# input_signal_conditioning.net
KiCad netlist of a schematic drawn in Altium Designer
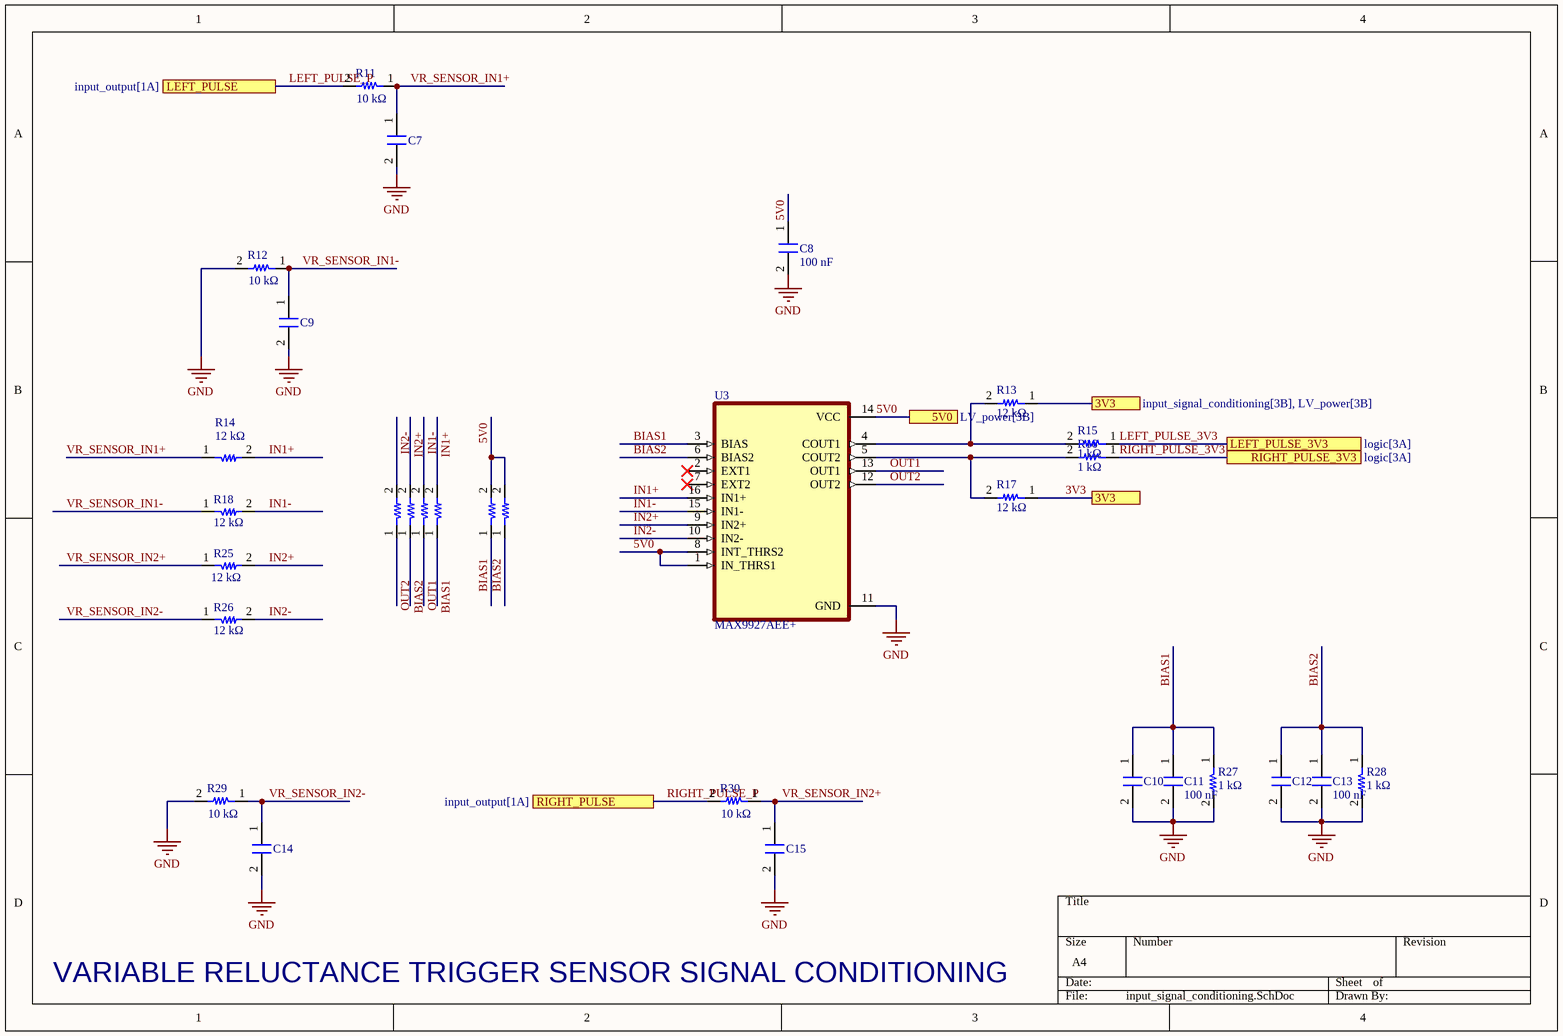
[diagram p0: input_signal_conditioning.SchDoc]

(export (version "E")
  (design (tool "Eeschema 10.0.6"))
  (components
    (comp (ref "C7")
      (value "Capacitor_0402")
      (footprint "0402_fp")
      (libsource (lib "RC_sch") (part "Capacitor_0402"))
    )
    (comp (ref "C8")
      (value "100 nF")
      (footprint "0402_fp")
      (fields (field (name "Comment") "Capacitor_0402"))
      (libsource (lib "RC_sch") (part "Capacitor_0402"))
    )
    (comp (ref "C9")
      (value "Capacitor_0402")
      (footprint "0402_fp")
      (libsource (lib "RC_sch") (part "Capacitor_0402"))
    )
    (comp (ref "C10")
      (value "Capacitor_0603")
      (footprint "0603_FP")
      (libsource (lib "RC_sch") (part "Capacitor_0603"))
    )
    (comp (ref "C11")
      (value "100 nF")
      (footprint "0402_fp")
      (fields (field (name "Comment") "Capacitor_0402"))
      (libsource (lib "RC_sch") (part "Capacitor_0402"))
    )
    (comp (ref "C12")
      (value "Capacitor_0603")
      (footprint "0603_FP")
      (libsource (lib "RC_sch") (part "Capacitor_0603"))
    )
    (comp (ref "C13")
      (value "100 nF")
      (footprint "0402_fp")
      (fields (field (name "Comment") "Capacitor_0402"))
      (libsource (lib "RC_sch") (part "Capacitor_0402"))
    )
    (comp (ref "C14")
      (value "Capacitor_0402")
      (footprint "0402_fp")
      (libsource (lib "RC_sch") (part "Capacitor_0402"))
    )
    (comp (ref "C15")
      (value "Capacitor_0402")
      (footprint "0402_fp")
      (libsource (lib "RC_sch") (part "Capacitor_0402"))
    )
    (comp (ref "R11")
      (value "10 kΩ")
      (footprint "0402_fp")
      (fields (field (name "Comment") "Resistor_0402"))
      (libsource (lib "RC_sch") (part "Resistor_0402"))
    )
    (comp (ref "R12")
      (value "10 kΩ")
      (footprint "0402_fp")
      (fields (field (name "Comment") "Resistor_0402"))
      (libsource (lib "RC_sch") (part "Resistor_0402"))
    )
    (comp (ref "R13")
      (value "12 kΩ")
      (footprint "0402_fp")
      (fields (field (name "Comment") "Resistor_0402"))
      (libsource (lib "RC_sch") (part "Resistor_0402"))
    )
    (comp (ref "R14")
      (value "12 kΩ")
      (footprint "0402_fp")
      (fields (field (name "Comment") "Resistor_0402"))
      (libsource (lib "RC_sch") (part "Resistor_0402"))
    )
    (comp (ref "R15")
      (value "1 kΩ")
      (footprint "0402_fp")
      (fields (field (name "Comment") "Resistor_0402"))
      (libsource (lib "RC_sch") (part "Resistor_0402"))
    )
    (comp (ref "R16")
      (value "1 kΩ")
      (footprint "0402_fp")
      (fields (field (name "Comment") "Resistor_0402"))
      (libsource (lib "RC_sch") (part "Resistor_0402"))
    )
    (comp (ref "R17")
      (value "12 kΩ")
      (footprint "0402_fp")
      (fields (field (name "Comment") "Resistor_0402"))
      (libsource (lib "RC_sch") (part "Resistor_0402"))
    )
    (comp (ref "R18")
      (value "12 kΩ")
      (footprint "0402_fp")
      (fields (field (name "Comment") "Resistor_0402"))
      (libsource (lib "RC_sch") (part "Resistor_0402"))
    )
    (comp (ref "R19")
      (value "Resistor_0402")
      (footprint "0402_fp")
      (libsource (lib "RC_sch") (part "Resistor_0402"))
    )
    (comp (ref "R20")
      (value "Resistor_0402")
      (footprint "0402_fp")
      (libsource (lib "RC_sch") (part "Resistor_0402"))
    )
    (comp (ref "R21")
      (value "Resistor_0402")
      (footprint "0402_fp")
      (libsource (lib "RC_sch") (part "Resistor_0402"))
    )
    (comp (ref "R22")
      (value "Resistor_0402")
      (footprint "0402_fp")
      (libsource (lib "RC_sch") (part "Resistor_0402"))
    )
    (comp (ref "R23")
      (value "Resistor_0402")
      (footprint "0402_fp")
      (libsource (lib "RC_sch") (part "Resistor_0402"))
    )
    (comp (ref "R24")
      (value "Resistor_0402")
      (footprint "0402_fp")
      (libsource (lib "RC_sch") (part "Resistor_0402"))
    )
    (comp (ref "R25")
      (value "12 kΩ")
      (footprint "0402_fp")
      (fields (field (name "Comment") "Resistor_0402"))
      (libsource (lib "RC_sch") (part "Resistor_0402"))
    )
    (comp (ref "R26")
      (value "12 kΩ")
      (footprint "0402_fp")
      (fields (field (name "Comment") "Resistor_0402"))
      (libsource (lib "RC_sch") (part "Resistor_0402"))
    )
    (comp (ref "R27")
      (value "1 kΩ")
      (footprint "0402_fp")
      (fields (field (name "Comment") "Resistor_0402"))
      (libsource (lib "RC_sch") (part "Resistor_0402"))
    )
    (comp (ref "R28")
      (value "1 kΩ")
      (footprint "0402_fp")
      (fields (field (name "Comment") "Resistor_0402"))
      (libsource (lib "RC_sch") (part "Resistor_0402"))
    )
    (comp (ref "R29")
      (value "10 kΩ")
      (footprint "0402_fp")
      (fields (field (name "Comment") "Resistor_0402"))
      (libsource (lib "RC_sch") (part "Resistor_0402"))
    )
    (comp (ref "R30")
      (value "10 kΩ")
      (footprint "0402_fp")
      (fields (field (name "Comment") "Resistor_0402"))
      (libsource (lib "RC_sch") (part "Resistor_0402"))
    )
    (comp (ref "U3")
      (value "MAX9927AEE+")
      (footprint "SOP63P602X175-16N")
      (description "Variable-Reluctance Sensor Interface with Differential Input and Adaptive Peak Threshold")
      (fields (field (name "MF") "Analog Devices"))
      (libsource (lib "MAX9927AEE+") (part "MAX9927AEE+"))
    )
  )
  (nets
    (net (code "1") (name "/3V3") (class "Default")
      (node (ref "R13") (pin "1") (pinfunction "1_1") (pintype "passive"))
      (node (ref "R17") (pin "1") (pinfunction "1_1") (pintype "passive"))
    )
    (net (code "2") (name "/5V0") (class "Default")
      (node (ref "C8") (pin "1") (pinfunction "1_1") (pintype "passive"))
      (node (ref "R23") (pin "2") (pinfunction "2_2") (pintype "passive"))
      (node (ref "R24") (pin "2") (pinfunction "2_2") (pintype "passive"))
      (node (ref "U3") (pin "1") (pinfunction "IN_THRS1_1") (pintype "input"))
      (node (ref "U3") (pin "14") (pinfunction "VCC_14") (pintype "power_in"))
      (node (ref "U3") (pin "8") (pinfunction "INT_THRS2_8") (pintype "input"))
    )
    (net (code "3") (name "/BIAS1") (class "Default")
      (node (ref "C10") (pin "1") (pinfunction "1_1") (pintype "passive"))
      (node (ref "C11") (pin "1") (pinfunction "1_1") (pintype "passive"))
      (node (ref "R22") (pin "1") (pinfunction "1_1") (pintype "passive"))
      (node (ref "R23") (pin "1") (pinfunction "1_1") (pintype "passive"))
      (node (ref "R27") (pin "1") (pinfunction "1_1") (pintype "passive"))
      (node (ref "U3") (pin "3") (pinfunction "BIAS_3") (pintype "input"))
    )
    (net (code "4") (name "/BIAS2") (class "Default")
      (node (ref "C12") (pin "1") (pinfunction "1_1") (pintype "passive"))
      (node (ref "C13") (pin "1") (pinfunction "1_1") (pintype "passive"))
      (node (ref "R20") (pin "1") (pinfunction "1_1") (pintype "passive"))
      (node (ref "R24") (pin "1") (pinfunction "1_1") (pintype "passive"))
      (node (ref "R28") (pin "1") (pinfunction "1_1") (pintype "passive"))
      (node (ref "U3") (pin "6") (pinfunction "BIAS2_6") (pintype "input"))
    )
    (net (code "5") (name "/IN1+") (class "Default")
      (node (ref "R14") (pin "2") (pinfunction "2_2") (pintype "passive"))
      (node (ref "R22") (pin "2") (pinfunction "2_2") (pintype "passive"))
      (node (ref "U3") (pin "16") (pinfunction "IN1+_16") (pintype "input"))
    )
    (net (code "6") (name "/IN1-") (class "Default")
      (node (ref "R18") (pin "2") (pinfunction "2_2") (pintype "passive"))
      (node (ref "R21") (pin "2") (pinfunction "2_2") (pintype "passive"))
      (node (ref "U3") (pin "15") (pinfunction "IN1-_15") (pintype "input"))
    )
    (net (code "7") (name "/IN2+") (class "Default")
      (node (ref "R20") (pin "2") (pinfunction "2_2") (pintype "passive"))
      (node (ref "R25") (pin "2") (pinfunction "2_2") (pintype "passive"))
      (node (ref "U3") (pin "9") (pinfunction "IN2+_9") (pintype "input"))
    )
    (net (code "8") (name "/IN2-") (class "Default")
      (node (ref "R19") (pin "2") (pinfunction "2_2") (pintype "passive"))
      (node (ref "R26") (pin "2") (pinfunction "2_2") (pintype "passive"))
      (node (ref "U3") (pin "10") (pinfunction "IN2-_10") (pintype "input"))
    )
    (net (code "9") (name "/LEFT_PULSE_3V3") (class "Default")
      (node (ref "R15") (pin "1") (pinfunction "1_1") (pintype "passive"))
    )
    (net (code "10") (name "/LEFT_PULSE_P") (class "Default")
      (node (ref "R11") (pin "2") (pinfunction "2_2") (pintype "passive"))
    )
    (net (code "11") (name "/OUT1") (class "Default")
      (node (ref "R21") (pin "1") (pinfunction "1_1") (pintype "passive"))
      (node (ref "U3") (pin "13") (pinfunction "OUT1_13") (pintype "output"))
    )
    (net (code "12") (name "/OUT2") (class "Default")
      (node (ref "R19") (pin "1") (pinfunction "1_1") (pintype "passive"))
      (node (ref "U3") (pin "12") (pinfunction "OUT2_12") (pintype "output"))
    )
    (net (code "13") (name "/RIGHT_PULSE_3V3") (class "Default")
      (node (ref "R16") (pin "1") (pinfunction "1_1") (pintype "passive"))
    )
    (net (code "14") (name "/RIGHT_PULSE_P") (class "Default")
      (node (ref "R30") (pin "2") (pinfunction "2_2") (pintype "passive"))
    )
    (net (code "15") (name "/VR_SENSOR_IN1+") (class "Default")
      (node (ref "C7") (pin "1") (pinfunction "1_1") (pintype "passive"))
      (node (ref "R11") (pin "1") (pinfunction "1_1") (pintype "passive"))
      (node (ref "R14") (pin "1") (pinfunction "1_1") (pintype "passive"))
    )
    (net (code "16") (name "/VR_SENSOR_IN1-") (class "Default")
      (node (ref "C9") (pin "1") (pinfunction "1_1") (pintype "passive"))
      (node (ref "R12") (pin "1") (pinfunction "1_1") (pintype "passive"))
      (node (ref "R18") (pin "1") (pinfunction "1_1") (pintype "passive"))
    )
    (net (code "17") (name "/VR_SENSOR_IN2+") (class "Default")
      (node (ref "C15") (pin "1") (pinfunction "1_1") (pintype "passive"))
      (node (ref "R25") (pin "1") (pinfunction "1_1") (pintype "passive"))
      (node (ref "R30") (pin "1") (pinfunction "1_1") (pintype "passive"))
    )
    (net (code "18") (name "/VR_SENSOR_IN2-") (class "Default")
      (node (ref "C14") (pin "1") (pinfunction "1_1") (pintype "passive"))
      (node (ref "R26") (pin "1") (pinfunction "1_1") (pintype "passive"))
      (node (ref "R29") (pin "1") (pinfunction "1_1") (pintype "passive"))
    )
    (net (code "19") (name "GND") (class "Default")
      (node (ref "C10") (pin "2") (pinfunction "2_2") (pintype "passive"))
      (node (ref "C11") (pin "2") (pinfunction "2_2") (pintype "passive"))
      (node (ref "C12") (pin "2") (pinfunction "2_2") (pintype "passive"))
      (node (ref "C13") (pin "2") (pinfunction "2_2") (pintype "passive"))
      (node (ref "C14") (pin "2") (pinfunction "2_2") (pintype "passive"))
      (node (ref "C15") (pin "2") (pinfunction "2_2") (pintype "passive"))
      (node (ref "C7") (pin "2") (pinfunction "2_2") (pintype "passive"))
      (node (ref "C8") (pin "2") (pinfunction "2_2") (pintype "passive"))
      (node (ref "C9") (pin "2") (pinfunction "2_2") (pintype "passive"))
      (node (ref "R12") (pin "2") (pinfunction "2_2") (pintype "passive"))
      (node (ref "R27") (pin "2") (pinfunction "2_2") (pintype "passive"))
      (node (ref "R28") (pin "2") (pinfunction "2_2") (pintype "passive"))
      (node (ref "R29") (pin "2") (pinfunction "2_2") (pintype "passive"))
      (node (ref "U3") (pin "11") (pinfunction "GND_11") (pintype "power_in"))
    )
    (net (code "20") (name "Net-(U3-COUT1)") (class "Default")
      (node (ref "R13") (pin "2") (pinfunction "2_2") (pintype "passive"))
      (node (ref "R15") (pin "2") (pinfunction "2_2") (pintype "passive"))
      (node (ref "U3") (pin "4") (pinfunction "COUT1_4") (pintype "output"))
    )
    (net (code "21") (name "Net-(U3-COUT2)") (class "Default")
      (node (ref "R16") (pin "2") (pinfunction "2_2") (pintype "passive"))
      (node (ref "R17") (pin "2") (pinfunction "2_2") (pintype "passive"))
      (node (ref "U3") (pin "5") (pinfunction "COUT2_5") (pintype "output"))
    )
    (net (code "22") (name "unconnected-(U3-EXT1-Pad2)") (class "Default")
      (node (ref "U3") (pin "2") (pinfunction "EXT1_2") (pintype "input+no_connect"))
    )
    (net (code "23") (name "unconnected-(U3-EXT2-Pad7)") (class "Default")
      (node (ref "U3") (pin "7") (pinfunction "EXT2_7") (pintype "input+no_connect"))
    )
  )
)
